# wiiuusbc.net
KiCad netlist of a schematic drawn in EAGLE
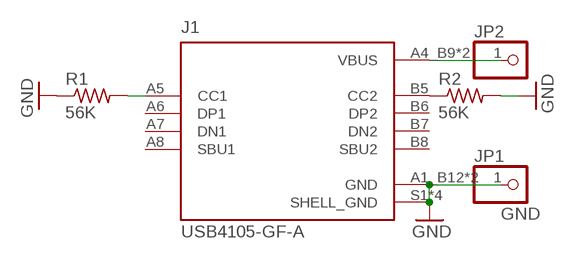
[diagram p0: schematic, sheet 1]

(export (version "E")
  (design (tool "Eeschema 10.0.6"))
  (components
    (comp (ref "J1")
      (value "USB4105-GF-A")
      (footprint "eagle-import:GCT_USB4105-GF-A")
      (fields (field (name "MF") "GCT"))
      (libsource (lib "eagle-import") (part "USB4105-GF-A"))
    )
    (comp (ref "JP1")
      (value "PINHD-1X1")
      (footprint "eagle-import:1X01")
      (libsource (lib "eagle-import") (part "PINHD-1X1"))
    )
    (comp (ref "JP2")
      (value "PINHD-1X1")
      (footprint "eagle-import:1X01")
      (libsource (lib "eagle-import") (part "PINHD-1X1"))
    )
    (comp (ref "R1")
      (value "56K")
      (footprint "eagle-import:R0402")
      (libsource (lib "eagle-import") (part "R-US_R0402"))
    )
    (comp (ref "R2")
      (value "56K")
      (footprint "eagle-import:R0402")
      (libsource (lib "eagle-import") (part "R-US_R0402"))
    )
  )
  (nets
    (net (code "1") (name "GND") (class "Default")
      (node (ref "J1") (pin "A1_B12") (pinfunction "GND_A1_B12") (pintype "power_in"))
      (node (ref "J1") (pin "B1_A12") (pinfunction "GND_B1_A12") (pintype "power_in"))
      (node (ref "J1") (pin "S1") (pinfunction "SHELL_GND_S1") (pintype "power_in"))
      (node (ref "J1") (pin "S2") (pinfunction "SHELL_GND_S2") (pintype "power_in"))
      (node (ref "J1") (pin "S3") (pinfunction "SHELL_GND_S3") (pintype "power_in"))
      (node (ref "J1") (pin "S4") (pinfunction "SHELL_GND_S4") (pintype "power_in"))
      (node (ref "JP1") (pin "1") (pinfunction "1_1") (pintype "passive"))
      (node (ref "R1") (pin "1") (pinfunction "1_1") (pintype "passive"))
      (node (ref "R2") (pin "2") (pinfunction "2_2") (pintype "passive"))
    )
    (net (code "2") (name "Net-(J1-CC1)") (class "Default")
      (node (ref "J1") (pin "A5") (pinfunction "CC1_A5") (pintype "bidirectional"))
      (node (ref "R1") (pin "2") (pinfunction "2_2") (pintype "passive"))
    )
    (net (code "3") (name "Net-(J1-CC2)") (class "Default")
      (node (ref "J1") (pin "B5") (pinfunction "CC2_B5") (pintype "bidirectional"))
      (node (ref "R2") (pin "1") (pinfunction "1_1") (pintype "passive"))
    )
    (net (code "4") (name "Net-(J1-VBUS-PadA4_B9)") (class "Default")
      (node (ref "J1") (pin "A4_B9") (pinfunction "VBUS_A4_B9") (pintype "power_in"))
      (node (ref "J1") (pin "B4_A9") (pinfunction "VBUS_B4_A9") (pintype "power_in"))
      (node (ref "JP2") (pin "1") (pinfunction "1_1") (pintype "passive"))
    )
    (net (code "5") (name "unconnected-(J1-DN1-PadA7)") (class "Default")
      (node (ref "J1") (pin "A7") (pinfunction "DN1_A7") (pintype "bidirectional"))
    )
    (net (code "6") (name "unconnected-(J1-DN2-PadB7)") (class "Default")
      (node (ref "J1") (pin "B7") (pinfunction "DN2_B7") (pintype "bidirectional"))
    )
    (net (code "7") (name "unconnected-(J1-DP1-PadA6)") (class "Default")
      (node (ref "J1") (pin "A6") (pinfunction "DP1_A6") (pintype "bidirectional"))
    )
    (net (code "8") (name "unconnected-(J1-DP2-PadB6)") (class "Default")
      (node (ref "J1") (pin "B6") (pinfunction "DP2_B6") (pintype "bidirectional"))
    )
    (net (code "9") (name "unconnected-(J1-SBU1-PadA8)") (class "Default")
      (node (ref "J1") (pin "A8") (pinfunction "SBU1_A8") (pintype "bidirectional"))
    )
    (net (code "10") (name "unconnected-(J1-SBU2-PadB8)") (class "Default")
      (node (ref "J1") (pin "B8") (pinfunction "SBU2_B8") (pintype "bidirectional"))
    )
  )
)
